# capbot.net
KiCad netlist of a schematic drawn in EAGLE
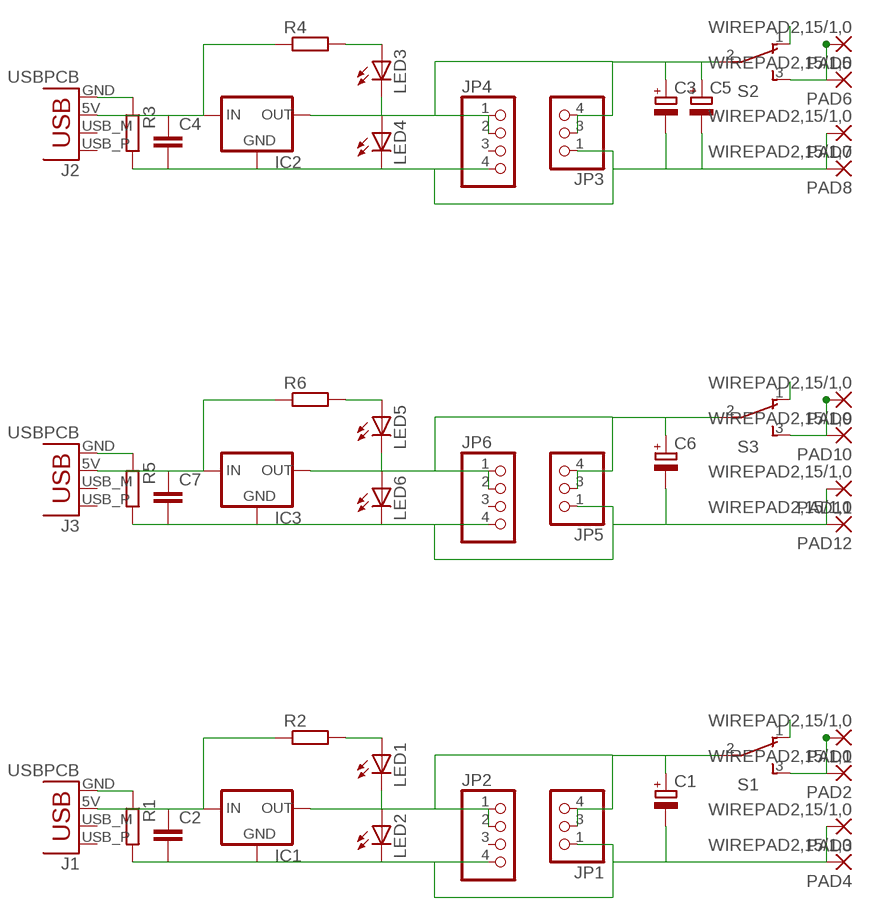
[diagram p0: schematic, sheet 1]

(export (version "E")
  (design (tool "Eeschema 10.0.6"))
  (components
    (comp (ref "C1")
      (value "CPOL-EUE5-10.5")
      (footprint "eagle-import:E5-10,5")
      (libsource (lib "eagle-import") (part "CPOL-EUE5-10.5"))
    )
    (comp (ref "C2")
      (value "C-EUC1206")
      (footprint "eagle-import:C1206")
      (libsource (lib "eagle-import") (part "C-EUC1206"))
    )
    (comp (ref "C3")
      (value "CPOL-EUE5-10.5")
      (footprint "eagle-import:E5-10,5")
      (libsource (lib "eagle-import") (part "CPOL-EUE5-10.5"))
    )
    (comp (ref "C4")
      (value "C-EUC1206")
      (footprint "eagle-import:C1206")
      (libsource (lib "eagle-import") (part "C-EUC1206"))
    )
    (comp (ref "C5")
      (value "CPOL-EUE5-10.5")
      (footprint "eagle-import:E5-10,5")
      (libsource (lib "eagle-import") (part "CPOL-EUE5-10.5"))
    )
    (comp (ref "C6")
      (value "CPOL-EUE5-10.5")
      (footprint "eagle-import:E5-10,5")
      (libsource (lib "eagle-import") (part "CPOL-EUE5-10.5"))
    )
    (comp (ref "C7")
      (value "C-EUC1206")
      (footprint "eagle-import:C1206")
      (libsource (lib "eagle-import") (part "C-EUC1206"))
    )
    (comp (ref "IC1")
      (value "MCP1700INLINE")
      (footprint "eagle-import:TO92-INLINE")
      (libsource (lib "eagle-import") (part "MCP1700INLINE"))
    )
    (comp (ref "IC2")
      (value "MCP1700INLINE")
      (footprint "eagle-import:TO92-INLINE")
      (libsource (lib "eagle-import") (part "MCP1700INLINE"))
    )
    (comp (ref "IC3")
      (value "MCP1700INLINE")
      (footprint "eagle-import:TO92-INLINE")
      (libsource (lib "eagle-import") (part "MCP1700INLINE"))
    )
    (comp (ref "J1")
      (value "USBPCB")
      (footprint "eagle-import:USB-A-PCB")
      (libsource (lib "eagle-import") (part "USBPCB"))
    )
    (comp (ref "J2")
      (value "USBPCB")
      (footprint "eagle-import:USB-A-PCB")
      (libsource (lib "eagle-import") (part "USBPCB"))
    )
    (comp (ref "J3")
      (value "USBPCB")
      (footprint "eagle-import:USB-A-PCB")
      (libsource (lib "eagle-import") (part "USBPCB"))
    )
    (comp (ref "JP1")
      (value "PINHD-1X3-4GAP")
      (footprint "eagle-import:1X04_GAP2")
      (libsource (lib "eagle-import") (part "PINHD-1X3-4GAP"))
    )
    (comp (ref "JP2")
      (value "PINHD-1X4")
      (footprint "eagle-import:1X04_OFFSETDOWN")
      (libsource (lib "eagle-import") (part "PINHD-1X4"))
    )
    (comp (ref "JP3")
      (value "PINHD-1X3-4GAP")
      (footprint "eagle-import:1X04_GAP2")
      (libsource (lib "eagle-import") (part "PINHD-1X3-4GAP"))
    )
    (comp (ref "JP4")
      (value "PINHD-1X4")
      (footprint "eagle-import:1X04_OFFSETDOWN")
      (libsource (lib "eagle-import") (part "PINHD-1X4"))
    )
    (comp (ref "JP5")
      (value "PINHD-1X3-4GAP")
      (footprint "eagle-import:1X04_GAP2")
      (libsource (lib "eagle-import") (part "PINHD-1X3-4GAP"))
    )
    (comp (ref "JP6")
      (value "PINHD-1X4")
      (footprint "eagle-import:1X04_OFFSETDOWN")
      (libsource (lib "eagle-import") (part "PINHD-1X4"))
    )
    (comp (ref "LED1")
      (value "LED3MM-MOREFLAT")
      (footprint "eagle-import:LED3MM-MOREFLAT")
      (libsource (lib "eagle-import") (part "LED3MM-MOREFLAT"))
    )
    (comp (ref "LED2")
      (value "LED3MM-MOREFLAT")
      (footprint "eagle-import:LED3MM-MOREFLAT")
      (libsource (lib "eagle-import") (part "LED3MM-MOREFLAT"))
    )
    (comp (ref "LED3")
      (value "LED3MM-MOREFLAT")
      (footprint "eagle-import:LED3MM-MOREFLAT")
      (libsource (lib "eagle-import") (part "LED3MM-MOREFLAT"))
    )
    (comp (ref "LED4")
      (value "LED3MM-MOREFLAT")
      (footprint "eagle-import:LED3MM-MOREFLAT")
      (libsource (lib "eagle-import") (part "LED3MM-MOREFLAT"))
    )
    (comp (ref "LED5")
      (value "LED3MM-MOREFLAT")
      (footprint "eagle-import:LED3MM-MOREFLAT")
      (libsource (lib "eagle-import") (part "LED3MM-MOREFLAT"))
    )
    (comp (ref "LED6")
      (value "LED3MM-MOREFLAT")
      (footprint "eagle-import:LED3MM-MOREFLAT")
      (libsource (lib "eagle-import") (part "LED3MM-MOREFLAT"))
    )
    (comp (ref "PAD1")
      (value "WIREPAD2,15/1,0")
      (footprint "eagle-import:2,15_1,0")
      (libsource (lib "eagle-import") (part "WIREPAD2,15/1,0"))
    )
    (comp (ref "PAD2")
      (value "WIREPAD2,15/1,0")
      (footprint "eagle-import:2,15_1,0")
      (libsource (lib "eagle-import") (part "WIREPAD2,15/1,0"))
    )
    (comp (ref "PAD3")
      (value "WIREPAD2,15/1,0")
      (footprint "eagle-import:2,15_1,0")
      (libsource (lib "eagle-import") (part "WIREPAD2,15/1,0"))
    )
    (comp (ref "PAD4")
      (value "WIREPAD2,15/1,0")
      (footprint "eagle-import:2,15_1,0")
      (libsource (lib "eagle-import") (part "WIREPAD2,15/1,0"))
    )
    (comp (ref "PAD5")
      (value "WIREPAD2,15/1,0")
      (footprint "eagle-import:2,15_1,0")
      (libsource (lib "eagle-import") (part "WIREPAD2,15/1,0"))
    )
    (comp (ref "PAD6")
      (value "WIREPAD2,15/1,0")
      (footprint "eagle-import:2,15_1,0")
      (libsource (lib "eagle-import") (part "WIREPAD2,15/1,0"))
    )
    (comp (ref "PAD7")
      (value "WIREPAD2,15/1,0")
      (footprint "eagle-import:2,15_1,0")
      (libsource (lib "eagle-import") (part "WIREPAD2,15/1,0"))
    )
    (comp (ref "PAD8")
      (value "WIREPAD2,15/1,0")
      (footprint "eagle-import:2,15_1,0")
      (libsource (lib "eagle-import") (part "WIREPAD2,15/1,0"))
    )
    (comp (ref "PAD9")
      (value "WIREPAD2,15/1,0")
      (footprint "eagle-import:2,15_1,0")
      (libsource (lib "eagle-import") (part "WIREPAD2,15/1,0"))
    )
    (comp (ref "PAD10")
      (value "WIREPAD2,15/1,0")
      (footprint "eagle-import:2,15_1,0")
      (libsource (lib "eagle-import") (part "WIREPAD2,15/1,0"))
    )
    (comp (ref "PAD11")
      (value "WIREPAD2,15/1,0")
      (footprint "eagle-import:2,15_1,0")
      (libsource (lib "eagle-import") (part "WIREPAD2,15/1,0"))
    )
    (comp (ref "PAD12")
      (value "WIREPAD2,15/1,0")
      (footprint "eagle-import:2,15_1,0")
      (libsource (lib "eagle-import") (part "WIREPAD2,15/1,0"))
    )
    (comp (ref "R1")
      (value "R-EU_0207/7")
      (footprint "eagle-import:0207_7")
      (libsource (lib "eagle-import") (part "R-EU_0207/7"))
    )
    (comp (ref "R2")
      (value "R-EU_0207/5V")
      (footprint "eagle-import:0207_5V")
      (libsource (lib "eagle-import") (part "R-EU_0207/5V"))
    )
    (comp (ref "R3")
      (value "R-EU_0207/7")
      (footprint "eagle-import:0207_7")
      (libsource (lib "eagle-import") (part "R-EU_0207/7"))
    )
    (comp (ref "R4")
      (value "R-EU_0207/5V")
      (footprint "eagle-import:0207_5V")
      (libsource (lib "eagle-import") (part "R-EU_0207/5V"))
    )
    (comp (ref "R5")
      (value "R-EU_0207/7")
      (footprint "eagle-import:0207_7")
      (libsource (lib "eagle-import") (part "R-EU_0207/7"))
    )
    (comp (ref "R6")
      (value "R-EU_0207/5V")
      (footprint "eagle-import:0207_5V")
      (libsource (lib "eagle-import") (part "R-EU_0207/5V"))
    )
    (comp (ref "S1")
      (value "TL36PO")
      (footprint "eagle-import:TL3XPO")
      (libsource (lib "eagle-import") (part "TL36PO"))
    )
    (comp (ref "S2")
      (value "TL36PO")
      (footprint "eagle-import:TL3XPO")
      (libsource (lib "eagle-import") (part "TL36PO"))
    )
    (comp (ref "S3")
      (value "TL36PO")
      (footprint "eagle-import:TL3XPO")
      (libsource (lib "eagle-import") (part "TL36PO"))
    )
  )
  (nets
    (net (code "1") (name "Net-(IC1-GND)") (class "Default")
      (node (ref "C1") (pin "-") (pinfunction "-_-") (pintype "passive"))
      (node (ref "C2") (pin "2") (pinfunction "2_2") (pintype "passive"))
      (node (ref "IC1") (pin "1") (pinfunction "GND_1") (pintype "input"))
      (node (ref "JP1") (pin "1") (pinfunction "1_1") (pintype "passive"))
      (node (ref "JP2") (pin "4") (pinfunction "4_4") (pintype "passive"))
      (node (ref "LED2") (pin "K") (pinfunction "C_K") (pintype "passive"))
      (node (ref "PAD3") (pin "1") (pinfunction "P_1") (pintype "passive"))
      (node (ref "PAD4") (pin "1") (pinfunction "P_1") (pintype "passive"))
      (node (ref "R1") (pin "2") (pinfunction "2_2") (pintype "passive"))
    )
    (net (code "2") (name "Net-(IC1-IN)") (class "Default")
      (node (ref "C2") (pin "1") (pinfunction "1_1") (pintype "passive"))
      (node (ref "IC1") (pin "2") (pinfunction "IN_2") (pintype "input"))
      (node (ref "J1") (pin "5V") (pinfunction "VBUS_5V") (pintype "bidirectional"))
      (node (ref "R2") (pin "1") (pinfunction "1_1") (pintype "passive"))
    )
    (net (code "3") (name "Net-(IC1-OUT)") (class "Default")
      (node (ref "C1") (pin "+") (pinfunction "+_+") (pintype "passive"))
      (node (ref "IC1") (pin "3") (pinfunction "OUT_3") (pintype "passive"))
      (node (ref "JP1") (pin "3") (pinfunction "2_3") (pintype "passive"))
      (node (ref "JP1") (pin "4") (pinfunction "3_4") (pintype "passive"))
      (node (ref "JP2") (pin "1") (pinfunction "1_1") (pintype "passive"))
      (node (ref "JP2") (pin "2") (pinfunction "2_2") (pintype "passive"))
      (node (ref "S1") (pin "2") (pinfunction "P_2") (pintype "passive"))
    )
    (net (code "4") (name "Net-(IC2-GND)") (class "Default")
      (node (ref "C3") (pin "-") (pinfunction "-_-") (pintype "passive"))
      (node (ref "C4") (pin "2") (pinfunction "2_2") (pintype "passive"))
      (node (ref "C5") (pin "-") (pinfunction "-_-") (pintype "passive"))
      (node (ref "IC2") (pin "1") (pinfunction "GND_1") (pintype "input"))
      (node (ref "JP3") (pin "1") (pinfunction "1_1") (pintype "passive"))
      (node (ref "JP4") (pin "4") (pinfunction "4_4") (pintype "passive"))
      (node (ref "LED4") (pin "K") (pinfunction "C_K") (pintype "passive"))
      (node (ref "PAD7") (pin "1") (pinfunction "P_1") (pintype "passive"))
      (node (ref "PAD8") (pin "1") (pinfunction "P_1") (pintype "passive"))
      (node (ref "R3") (pin "2") (pinfunction "2_2") (pintype "passive"))
    )
    (net (code "5") (name "Net-(IC2-IN)") (class "Default")
      (node (ref "C4") (pin "1") (pinfunction "1_1") (pintype "passive"))
      (node (ref "IC2") (pin "2") (pinfunction "IN_2") (pintype "input"))
      (node (ref "J2") (pin "5V") (pinfunction "VBUS_5V") (pintype "bidirectional"))
      (node (ref "R4") (pin "1") (pinfunction "1_1") (pintype "passive"))
    )
    (net (code "6") (name "Net-(IC2-OUT)") (class "Default")
      (node (ref "C3") (pin "+") (pinfunction "+_+") (pintype "passive"))
      (node (ref "C5") (pin "+") (pinfunction "+_+") (pintype "passive"))
      (node (ref "IC2") (pin "3") (pinfunction "OUT_3") (pintype "passive"))
      (node (ref "JP3") (pin "3") (pinfunction "2_3") (pintype "passive"))
      (node (ref "JP3") (pin "4") (pinfunction "3_4") (pintype "passive"))
      (node (ref "JP4") (pin "1") (pinfunction "1_1") (pintype "passive"))
      (node (ref "JP4") (pin "2") (pinfunction "2_2") (pintype "passive"))
      (node (ref "S2") (pin "2") (pinfunction "P_2") (pintype "passive"))
    )
    (net (code "7") (name "Net-(IC3-GND)") (class "Default")
      (node (ref "C6") (pin "-") (pinfunction "-_-") (pintype "passive"))
      (node (ref "C7") (pin "2") (pinfunction "2_2") (pintype "passive"))
      (node (ref "IC3") (pin "1") (pinfunction "GND_1") (pintype "input"))
      (node (ref "JP5") (pin "1") (pinfunction "1_1") (pintype "passive"))
      (node (ref "JP6") (pin "4") (pinfunction "4_4") (pintype "passive"))
      (node (ref "LED6") (pin "K") (pinfunction "C_K") (pintype "passive"))
      (node (ref "PAD11") (pin "1") (pinfunction "P_1") (pintype "passive"))
      (node (ref "PAD12") (pin "1") (pinfunction "P_1") (pintype "passive"))
      (node (ref "R5") (pin "2") (pinfunction "2_2") (pintype "passive"))
    )
    (net (code "8") (name "Net-(IC3-IN)") (class "Default")
      (node (ref "C7") (pin "1") (pinfunction "1_1") (pintype "passive"))
      (node (ref "IC3") (pin "2") (pinfunction "IN_2") (pintype "input"))
      (node (ref "J3") (pin "5V") (pinfunction "VBUS_5V") (pintype "bidirectional"))
      (node (ref "R6") (pin "1") (pinfunction "1_1") (pintype "passive"))
    )
    (net (code "9") (name "Net-(IC3-OUT)") (class "Default")
      (node (ref "C6") (pin "+") (pinfunction "+_+") (pintype "passive"))
      (node (ref "IC3") (pin "3") (pinfunction "OUT_3") (pintype "passive"))
      (node (ref "JP5") (pin "3") (pinfunction "2_3") (pintype "passive"))
      (node (ref "JP5") (pin "4") (pinfunction "3_4") (pintype "passive"))
      (node (ref "JP6") (pin "1") (pinfunction "1_1") (pintype "passive"))
      (node (ref "JP6") (pin "2") (pinfunction "2_2") (pintype "passive"))
      (node (ref "S3") (pin "2") (pinfunction "P_2") (pintype "passive"))
    )
    (net (code "10") (name "Net-(J1-PadGND)") (class "Default")
      (node (ref "J1") (pin "GND") (pinfunction "GND_GND") (pintype "bidirectional"))
      (node (ref "R1") (pin "1") (pinfunction "1_1") (pintype "passive"))
    )
    (net (code "11") (name "Net-(J2-PadGND)") (class "Default")
      (node (ref "J2") (pin "GND") (pinfunction "GND_GND") (pintype "bidirectional"))
      (node (ref "R3") (pin "1") (pinfunction "1_1") (pintype "passive"))
    )
    (net (code "12") (name "Net-(J3-PadGND)") (class "Default")
      (node (ref "J3") (pin "GND") (pinfunction "GND_GND") (pintype "bidirectional"))
      (node (ref "R5") (pin "1") (pinfunction "1_1") (pintype "passive"))
    )
    (net (code "13") (name "Net-(LED1-C)") (class "Default")
      (node (ref "LED1") (pin "K") (pinfunction "C_K") (pintype "passive"))
      (node (ref "LED2") (pin "A") (pinfunction "A_A") (pintype "passive"))
    )
    (net (code "14") (name "Net-(LED1-PadA)") (class "Default")
      (node (ref "LED1") (pin "A") (pinfunction "A_A") (pintype "passive"))
      (node (ref "R2") (pin "2") (pinfunction "2_2") (pintype "passive"))
    )
    (net (code "15") (name "Net-(LED3-C)") (class "Default")
      (node (ref "LED3") (pin "K") (pinfunction "C_K") (pintype "passive"))
      (node (ref "LED4") (pin "A") (pinfunction "A_A") (pintype "passive"))
    )
    (net (code "16") (name "Net-(LED3-PadA)") (class "Default")
      (node (ref "LED3") (pin "A") (pinfunction "A_A") (pintype "passive"))
      (node (ref "R4") (pin "2") (pinfunction "2_2") (pintype "passive"))
    )
    (net (code "17") (name "Net-(LED5-C)") (class "Default")
      (node (ref "LED5") (pin "K") (pinfunction "C_K") (pintype "passive"))
      (node (ref "LED6") (pin "A") (pinfunction "A_A") (pintype "passive"))
    )
    (net (code "18") (name "Net-(LED5-PadA)") (class "Default")
      (node (ref "LED5") (pin "A") (pinfunction "A_A") (pintype "passive"))
      (node (ref "R6") (pin "2") (pinfunction "2_2") (pintype "passive"))
    )
    (net (code "19") (name "Net-(PAD1-P)") (class "Default")
      (node (ref "PAD1") (pin "1") (pinfunction "P_1") (pintype "passive"))
      (node (ref "PAD2") (pin "1") (pinfunction "P_1") (pintype "passive"))
      (node (ref "S1") (pin "3") (pinfunction "S_3") (pintype "passive"))
    )
    (net (code "20") (name "Net-(PAD5-P)") (class "Default")
      (node (ref "PAD5") (pin "1") (pinfunction "P_1") (pintype "passive"))
      (node (ref "PAD6") (pin "1") (pinfunction "P_1") (pintype "passive"))
      (node (ref "S2") (pin "3") (pinfunction "S_3") (pintype "passive"))
    )
    (net (code "21") (name "Net-(PAD10-P)") (class "Default")
      (node (ref "PAD10") (pin "1") (pinfunction "P_1") (pintype "passive"))
      (node (ref "PAD9") (pin "1") (pinfunction "P_1") (pintype "passive"))
      (node (ref "S3") (pin "3") (pinfunction "S_3") (pintype "passive"))
    )
    (net (code "22") (name "unconnected-(J1-D+-PadUSB_P)") (class "Default")
      (node (ref "J1") (pin "USB_P") (pinfunction "D+_USB_P") (pintype "bidirectional"))
    )
    (net (code "23") (name "unconnected-(J1-D--PadUSB_M)") (class "Default")
      (node (ref "J1") (pin "USB_M") (pinfunction "D-_USB_M") (pintype "bidirectional"))
    )
    (net (code "24") (name "unconnected-(J2-D+-PadUSB_P)") (class "Default")
      (node (ref "J2") (pin "USB_P") (pinfunction "D+_USB_P") (pintype "bidirectional"))
    )
    (net (code "25") (name "unconnected-(J2-D--PadUSB_M)") (class "Default")
      (node (ref "J2") (pin "USB_M") (pinfunction "D-_USB_M") (pintype "bidirectional"))
    )
    (net (code "26") (name "unconnected-(J3-D+-PadUSB_P)") (class "Default")
      (node (ref "J3") (pin "USB_P") (pinfunction "D+_USB_P") (pintype "bidirectional"))
    )
    (net (code "27") (name "unconnected-(J3-D--PadUSB_M)") (class "Default")
      (node (ref "J3") (pin "USB_M") (pinfunction "D-_USB_M") (pintype "bidirectional"))
    )
    (net (code "28") (name "unconnected-(JP2-Pad3)") (class "Default")
      (node (ref "JP2") (pin "3") (pinfunction "3_3") (pintype "passive"))
    )
    (net (code "29") (name "unconnected-(JP4-Pad3)") (class "Default")
      (node (ref "JP4") (pin "3") (pinfunction "3_3") (pintype "passive"))
    )
    (net (code "30") (name "unconnected-(JP6-Pad3)") (class "Default")
      (node (ref "JP6") (pin "3") (pinfunction "3_3") (pintype "passive"))
    )
    (net (code "31") (name "unconnected-(S1-O-Pad1)") (class "Default")
      (node (ref "S1") (pin "1") (pinfunction "O_1") (pintype "passive"))
    )
    (net (code "32") (name "unconnected-(S2-O-Pad1)") (class "Default")
      (node (ref "S2") (pin "1") (pinfunction "O_1") (pintype "passive"))
    )
    (net (code "33") (name "unconnected-(S3-O-Pad1)") (class "Default")
      (node (ref "S3") (pin "1") (pinfunction "O_1") (pintype "passive"))
    )
  )
)
